# Can_Interface.net
KiCad netlist of a schematic drawn in Altium Designer
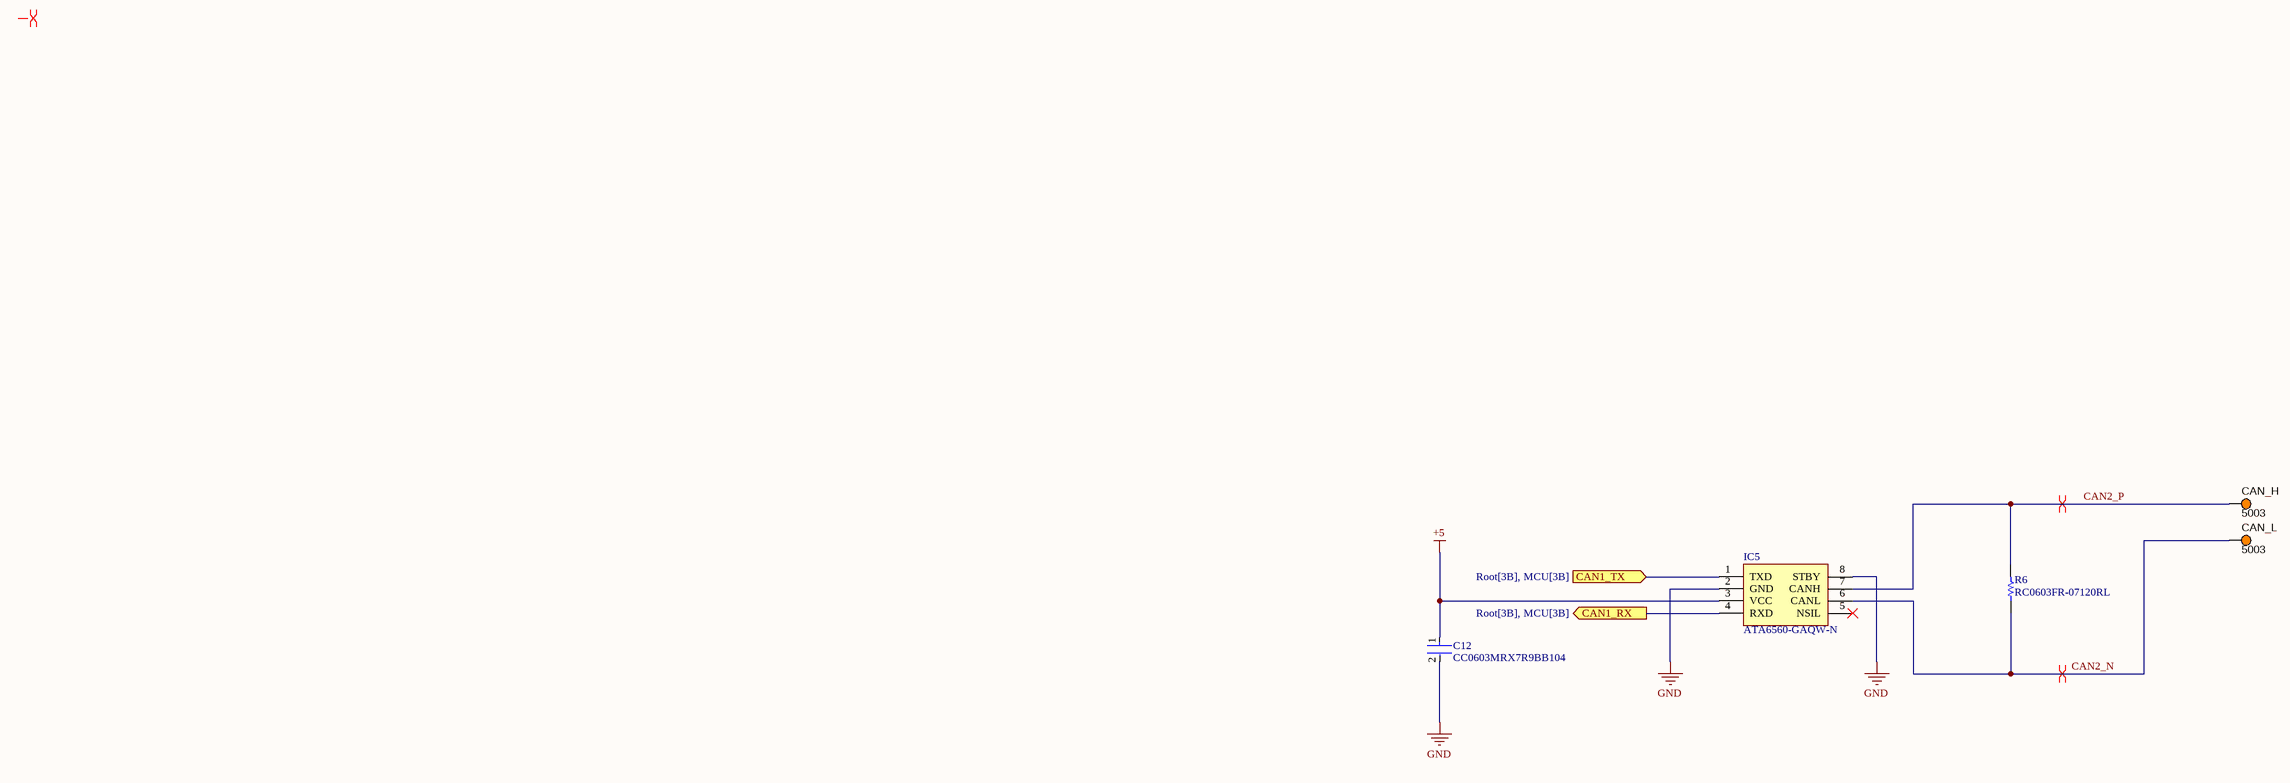
[diagram p0: Can_Interface.SchDoc]

(export (version "E")
  (design (tool "Eeschema 10.0.6"))
  (components
    (comp (ref "C12")
      (value "CC0603MRX7R9BB104")
      (footprint "FP-CC0603-DA-MFG")
      (description "CAP CER 0.1UF 50V X7R 0603")
      (fields
        (field (name "MANUFACTURER") "YAGEO")
        (field (name "OCTOPART") "https://octopart.com/cc0603mrx7r9bb104-yageo-67308423")
      )
      (libsource (lib "Altium Content Vault") (part "11868f565c42a9108669ba33697ecf6"))
    )
    (comp (ref "CAN_H")
      (value "5003")
      (footprint "KSTN-5003")
      (description "Test Point, Orange, Height 4.6 mm, Tail Length 3 mm, 1-Pin THD, RoHS")
      (fields (field (name "MANUFACTURER") "Keystone"))
      (libsource (lib "Daniel Wang") (part "TESTPOINT_ORANGE"))
    )
    (comp (ref "CAN_L")
      (value "5003")
      (footprint "KSTN-5003")
      (description "Test Point, Orange, Height 4.6 mm, Tail Length 3 mm, 1-Pin THD, RoHS")
      (fields (field (name "MANUFACTURER") "Keystone"))
      (libsource (lib "Daniel Wang") (part "TESTPOINT_ORANGE"))
    )
    (comp (ref "IC5")
      (value "ATA6560-GAQW-N")
      (footprint "SOIC8_4P9X3P9MC_MCH")
      (description "Integrated Circuit")
      (fields (field (name "MOUSER PART NUMBER") "579-ATA6560-GAQW-N"))
      (libsource (lib "*") (part "ATA6560-GAQW-N"))
    )
    (comp (ref "R6")
      (value "RC0603FR-07120RL")
      (footprint "RESC1608X55X25NL10T15")
      (description "Chip Resistor, 120 Ohm, +/- 1%, 100 mW, -55 to 155 degC, 0603 (1608 Metric), RoHS, Tape and Reel")
      (libsource (lib "Altium Content Vault") (part "RES-2"))
    )
  )
  (nets
    (net (code "1") (name "+5") (class "Default")
      (node (ref "C12") (pin "1") (pinfunction "1_1") (pintype "passive"))
      (node (ref "IC5") (pin "3") (pinfunction "VCC_3") (pintype "passive"))
    )
    (net (code "2") (name "/CAN1_RX") (class "Default")
      (node (ref "IC5") (pin "4") (pinfunction "RXD_4") (pintype "passive"))
    )
    (net (code "3") (name "/CAN1_TX") (class "Default")
      (node (ref "IC5") (pin "1") (pinfunction "TXD_1") (pintype "passive"))
    )
    (net (code "4") (name "/CAN2_N") (class "Default")
      (node (ref "CAN_L") (pin "1") (pinfunction "1_1") (pintype "passive"))
      (node (ref "IC5") (pin "6") (pinfunction "CANL_6") (pintype "passive"))
      (node (ref "R6") (pin "1") (pinfunction "1_1") (pintype "passive"))
    )
    (net (code "5") (name "/CAN2_P") (class "Default")
      (node (ref "CAN_H") (pin "1") (pinfunction "1_1") (pintype "passive"))
      (node (ref "IC5") (pin "7") (pinfunction "CANH_7") (pintype "passive"))
      (node (ref "R6") (pin "2") (pinfunction "2_2") (pintype "passive"))
    )
    (net (code "6") (name "GND") (class "Default")
      (node (ref "C12") (pin "2") (pinfunction "2_2") (pintype "passive"))
      (node (ref "IC5") (pin "2") (pinfunction "GND_2") (pintype "passive"))
      (node (ref "IC5") (pin "8") (pinfunction "STBY_8") (pintype "passive"))
    )
    (net (code "7") (name "unconnected-(IC5-NSIL-Pad5)") (class "Default")
      (node (ref "IC5") (pin "5") (pinfunction "NSIL_5") (pintype "passive+no_connect"))
    )
  )
)
